# PWR_MGMT.net
KiCad netlist of a schematic drawn in Altium Designer
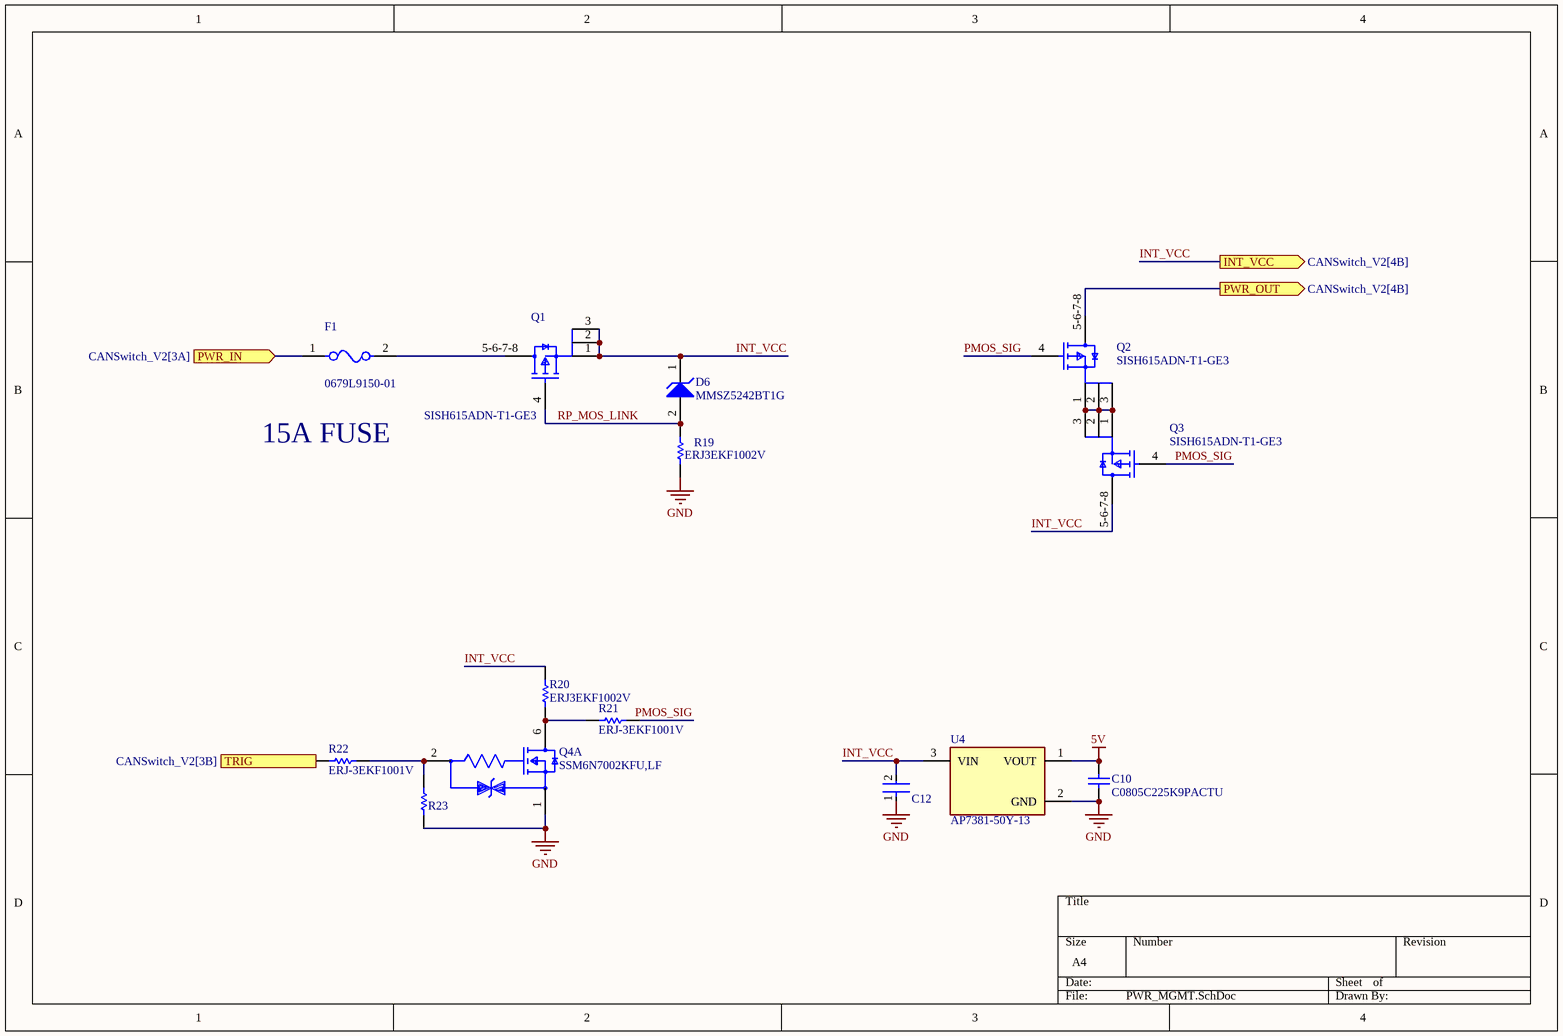
[diagram p0: PWR_MGMT.SchDoc]

(export (version "E")
  (design (tool "Eeschema 10.0.6"))
  (components
    (comp (ref "C10")
      (value "C0805C225K9PACTU")
      (footprint "CAPC2013X145X50ML20T25")
      (fields (field (name "MANUFACTURER") "Kemet"))
      (libsource (lib "Altium Content Vault") (part "CAP"))
    )
    (comp (ref "C12")
      (value "C0402C104K8PACTU")
      (footprint "FP-C0402-BB-MFG")
      (description "CAP CER 0.1UF 10V X5R 0402")
      (fields (field (name "MANUFACTURER") "Kemet") (field (name "TOLERANCE") "0.1"))
      (libsource (lib "Altium Content Vault") (part "b4654b650e69147ec39a6b967a45e02"))
    )
    (comp (ref "D6")
      (value "MMSZ5242BT1G")
      (footprint "ONSC-SOD-123-2-425-04_V")
      (description "Zener Voltage Regulator, 500 mW, 2-Pin SOD-123, Pb-Free, Tape and Reel")
      (fields (field (name "MANUFACTURER") "On Semiconductor"))
      (libsource (lib "Altium Content Vault") (part "ONSC-K1A2-2"))
    )
    (comp (ref "F1")
      (value "0679L9150-01")
      (footprint "FP-0679L-MFG")
      (description "FUSE BRD MNT 15A 125VAC/VDC")
      (fields
        (field (name "OCTOPART") "https://octopart.com/0679l9150-01-bel+fuse-70850665")
        (field (name "MANUFACTURER") "Bel Fuse")
      )
      (libsource (lib "Altium Content Vault") (part "5bcf9b9f640e542cf0359d10258e979"))
    )
    (comp (ref "Q1")
      (value "SISH615ADN-T1-GE3")
      (footprint "SISH615ADN-T1-GE3-Footprint-1")
      (description "Trans MOSFET P-CH 20V 22.1A 8-Pin PowerPAK 1212 EP T/R")
      (libsource (lib "uORocketry Hardware") (part "SISH615ADN-T1-GE3-Symbol-1"))
    )
    (comp (ref "Q2")
      (value "SISH615ADN-T1-GE3")
      (footprint "SISH615ADN-T1-GE3-Footprint-1")
      (description "Trans MOSFET P-CH 20V 22.1A 8-Pin PowerPAK 1212 EP T/R")
      (libsource (lib "uORocketry Hardware") (part "SISH615ADN-T1-GE3-Symbol-1"))
    )
    (comp (ref "Q3")
      (value "SISH615ADN-T1-GE3")
      (footprint "SISH615ADN-T1-GE3-Footprint-1")
      (description "Trans MOSFET P-CH 20V 22.1A 8-Pin PowerPAK 1212 EP T/R")
      (libsource (lib "uORocketry Hardware") (part "SISH615ADN-T1-GE3-Symbol-1"))
    )
    (comp (ref "Q4")
      (value "SSM6N7002KFU,LF")
      (footprint "FP-SSOP6-P-0_65A-MFG")
      (description "MOSFET 2N-CH 60V 0.3A")
      (libsource (lib "Altium Content Vault") (part "088aa6ac103fdeebe0d1c52ece6b7b9"))
    )
    (comp (ref "R19")
      (value "ERJ3EKF1002V")
      (footprint "RESC1609X55X30LL15T15")
      (description "Chip Resistor, 10 KOhm, +/- 1%, 0.1 W, -55 to 155 degC, 0603 (1608 Metric), RoHS, Tape and Reel")
      (fields (field (name "TOLERANCE") "1%") (field (name "MANUFACTURER") "Panasonic"))
      (libsource (lib "Altium Content Vault") (part "RES-2"))
    )
    (comp (ref "R20")
      (value "ERJ3EKF1002V")
      (footprint "RESC1609X55X30LL15T15")
      (description "Chip Resistor, 10 KOhm, +/- 1%, 0.1 W, -55 to 155 degC, 0603 (1608 Metric), RoHS, Tape and Reel")
      (fields (field (name "TOLERANCE") "1%") (field (name "MANUFACTURER") "Panasonic"))
      (libsource (lib "Altium Content Vault") (part "RES-2"))
    )
    (comp (ref "R21")
      (value "ERJ-3EKF1001V")
      (footprint "RESC1608X55X30LL15T15")
      (fields (field (name "MANUFACTURER") "Panasonic"))
      (libsource (lib "Altium Content Vault") (part "RES"))
    )
    (comp (ref "R22")
      (value "ERJ-3EKF1001V")
      (footprint "RESC1608X55X30LL15T15")
      (fields (field (name "MANUFACTURER") "Panasonic"))
      (libsource (lib "Altium Content Vault") (part "RES"))
    )
    (comp (ref "R23")
      (value "ERJ3EKF1002V")
      (footprint "RESC1609X55X30LL15T15")
      (description "Chip Resistor, 10 KOhm, +/- 1%, 0.1 W, -55 to 155 degC, 0603 (1608 Metric), RoHS, Tape and Reel")
      (fields (field (name "TOLERANCE") "1%") (field (name "MANUFACTURER") "Panasonic"))
      (libsource (lib "Altium Content Vault") (part "RES-2"))
    )
    (comp (ref "U4")
      (value "AP7381-50Y-13")
      (footprint "FP-SOT89-MFG")
      (description "IC REG LINEAR 5V 150MA SOT89")
      (fields
        (field (name "MANUFACTURER") "Diodes Inc.")
        (field (name "OCTOPART") "https://octopart.com/ap7381-50y-13-diodes+inc.-87775116")
      )
      (libsource (lib "Altium Content Vault") (part "4c3da590f2d7b1882ad42f13e6d336b"))
    )
  )
  (nets
    (net (code "1") (name "/INT_VCC") (class "Default")
      (node (ref "C12") (pin "2") (pinfunction "2_2") (pintype "passive"))
      (node (ref "D6") (pin "1") (pinfunction "K_1") (pintype "passive"))
      (node (ref "Q1") (pin "1") (pinfunction "S_1") (pintype "passive"))
      (node (ref "Q1") (pin "2") (pinfunction "S_2") (pintype "passive"))
      (node (ref "Q1") (pin "3") (pinfunction "S_3") (pintype "passive"))
      (node (ref "Q3") (pin "5-6-7-8") (pinfunction "D_5-6-7-8") (pintype "passive"))
      (node (ref "R20") (pin "2") (pinfunction "2_2") (pintype "passive"))
      (node (ref "U4") (pin "3") (pinfunction "VIN_3") (pintype "power_in"))
    )
    (net (code "2") (name "/PMOS_SIG") (class "Default")
      (node (ref "Q2") (pin "4") (pinfunction "G_4") (pintype "passive"))
      (node (ref "Q3") (pin "4") (pinfunction "G_4") (pintype "passive"))
      (node (ref "R21") (pin "1") (pinfunction "1_1") (pintype "passive"))
    )
    (net (code "3") (name "/PWR_IN") (class "Default")
      (node (ref "F1") (pin "1") (pinfunction "1_1") (pintype "passive"))
    )
    (net (code "4") (name "/PWR_OUT") (class "Default")
      (node (ref "Q2") (pin "5-6-7-8") (pinfunction "D_5-6-7-8") (pintype "passive"))
    )
    (net (code "5") (name "/RP_MOS_LINK") (class "Default")
      (node (ref "D6") (pin "2") (pinfunction "A_2") (pintype "passive"))
      (node (ref "Q1") (pin "4") (pinfunction "G_4") (pintype "passive"))
      (node (ref "R19") (pin "1") (pinfunction "1_1") (pintype "passive"))
    )
    (net (code "6") (name "/TRIG") (class "Default")
      (node (ref "R22") (pin "2") (pinfunction "2_2") (pintype "passive"))
    )
    (net (code "7") (name "5V") (class "Default")
      (node (ref "C10") (pin "2") (pinfunction "2_2") (pintype "passive"))
      (node (ref "U4") (pin "1") (pinfunction "VOUT_1") (pintype "power_in"))
    )
    (net (code "8") (name "GND") (class "Default")
      (node (ref "C10") (pin "1") (pinfunction "1_1") (pintype "passive"))
      (node (ref "C12") (pin "1") (pinfunction "1_1") (pintype "passive"))
      (node (ref "Q4") (pin "1") (pinfunction "Source1_1") (pintype "passive"))
      (node (ref "R19") (pin "2") (pinfunction "2_2") (pintype "passive"))
      (node (ref "R23") (pin "2") (pinfunction "2_2") (pintype "passive"))
      (node (ref "U4") (pin "2") (pinfunction "GND_2") (pintype "power_in"))
    )
    (net (code "9") (name "Net-(Q1-D)") (class "Default")
      (node (ref "F1") (pin "2") (pinfunction "2_2") (pintype "passive"))
      (node (ref "Q1") (pin "5-6-7-8") (pinfunction "D_5-6-7-8") (pintype "passive"))
    )
    (net (code "10") (name "Net-(Q2-S-Pad1)") (class "Default")
      (node (ref "Q2") (pin "1") (pinfunction "S_1") (pintype "passive"))
      (node (ref "Q2") (pin "2") (pinfunction "S_2") (pintype "passive"))
      (node (ref "Q2") (pin "3") (pinfunction "S_3") (pintype "passive"))
      (node (ref "Q3") (pin "1") (pinfunction "S_1") (pintype "passive"))
      (node (ref "Q3") (pin "2") (pinfunction "S_2") (pintype "passive"))
      (node (ref "Q3") (pin "3") (pinfunction "S_3") (pintype "passive"))
    )
    (net (code "11") (name "Net-(Q4A-Drain1)") (class "Default")
      (node (ref "Q4") (pin "6") (pinfunction "Drain1_6") (pintype "passive"))
      (node (ref "R20") (pin "1") (pinfunction "1_1") (pintype "passive"))
      (node (ref "R21") (pin "2") (pinfunction "2_2") (pintype "passive"))
    )
    (net (code "12") (name "Net-(Q4A-Gate1)") (class "Default")
      (node (ref "Q4") (pin "2") (pinfunction "Gate1_2") (pintype "passive"))
      (node (ref "R22") (pin "1") (pinfunction "1_1") (pintype "passive"))
      (node (ref "R23") (pin "1") (pinfunction "1_1") (pintype "passive"))
    )
  )
)
